# garden.net
KiCad netlist of a schematic drawn in EAGLE
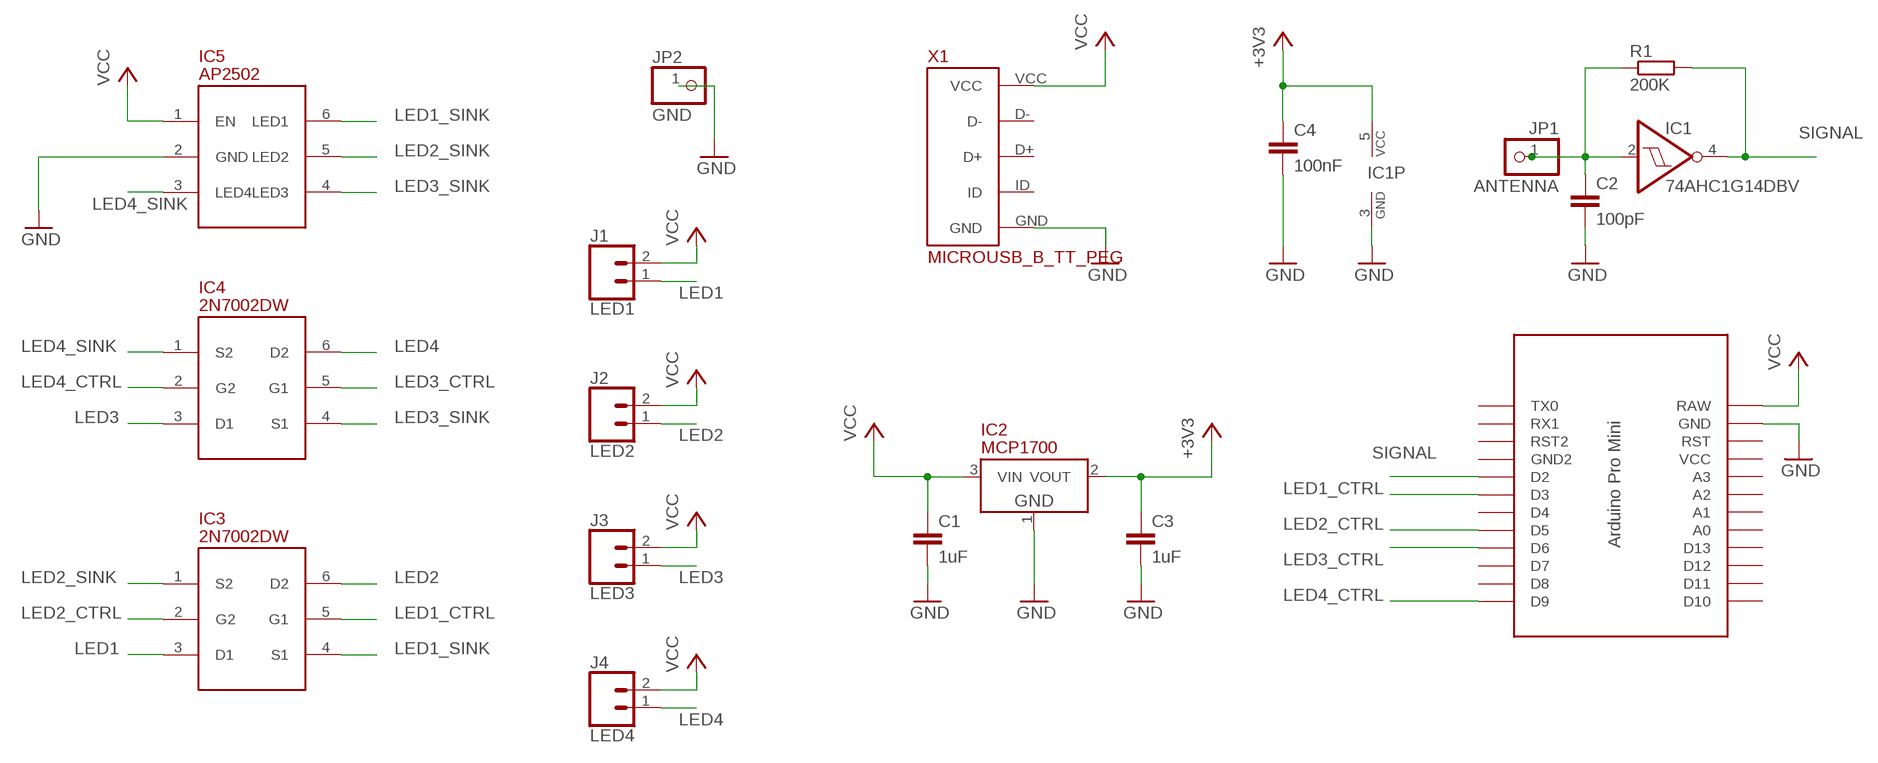
[diagram p0: schematic, sheet 1]

(export (version "E")
  (design (tool "Eeschema 10.0.6"))
  (components
    (comp (ref "C1")
      (value "1uF")
      (footprint "eagle-import:C0805")
      (libsource (lib "eagle-import") (part "C-EUC0805"))
    )
    (comp (ref "C2")
      (value "100pF")
      (footprint "eagle-import:C0805")
      (libsource (lib "eagle-import") (part "C-EUC0805"))
    )
    (comp (ref "C3")
      (value "1uF")
      (footprint "eagle-import:C0805")
      (libsource (lib "eagle-import") (part "C-EUC0805"))
    )
    (comp (ref "C4")
      (value "100nF")
      (footprint "eagle-import:C0805")
      (libsource (lib "eagle-import") (part "C-EUC0805"))
    )
    (comp (ref "IC1")
      (value "74AHC1G14DBV")
      (footprint "eagle-import:SOT23-5")
      (libsource (lib "eagle-import") (part "741G14DBVAHC"))
    )
    (comp (ref "IC2")
      (value "MCP1700")
      (footprint "eagle-import:SOT-23")
      (libsource (lib "eagle-import") (part "MCP1700"))
    )
    (comp (ref "IC3")
      (value "2N7002DW")
      (footprint "eagle-import:SOT363")
      (libsource (lib "eagle-import") (part "2N7002DW"))
    )
    (comp (ref "IC4")
      (value "2N7002DW")
      (footprint "eagle-import:SOT363")
      (libsource (lib "eagle-import") (part "2N7002DW"))
    )
    (comp (ref "IC5")
      (value "AP2502")
      (footprint "eagle-import:SOT-23-6")
      (libsource (lib "eagle-import") (part "AP2502"))
    )
    (comp (ref "J1")
      (value "LED1")
      (footprint "eagle-import:1X02")
      (libsource (lib "eagle-import") (part "CONN_02"))
    )
    (comp (ref "J2")
      (value "LED2")
      (footprint "eagle-import:1X02")
      (libsource (lib "eagle-import") (part "CONN_02"))
    )
    (comp (ref "J3")
      (value "LED3")
      (footprint "eagle-import:1X02")
      (libsource (lib "eagle-import") (part "CONN_02"))
    )
    (comp (ref "J4")
      (value "LED4")
      (footprint "eagle-import:1X02")
      (libsource (lib "eagle-import") (part "CONN_02"))
    )
    (comp (ref "JP1")
      (value "ANTENNA")
      (footprint "eagle-import:1X01")
      (libsource (lib "eagle-import") (part "PINHD-1X1"))
    )
    (comp (ref "JP2")
      (value "GND")
      (footprint "eagle-import:1X01")
      (libsource (lib "eagle-import") (part "PINHD-1X1"))
    )
    (comp (ref "R1")
      (value "200K")
      (footprint "eagle-import:R0805")
      (libsource (lib "eagle-import") (part "R-EU_R0805"))
    )
    (comp (ref "U$1")
      (value "PRO-MINI-TWO-SIDES-ONLY")
      (footprint "eagle-import:PRO-MINI-TWO-SIDES-ONLY")
      (libsource (lib "eagle-import") (part "PRO-MINI-TWO-SIDES-ONLY"))
    )
    (comp (ref "X1")
      (value "MICROUSB_B_TT_PEG")
      (footprint "eagle-import:MICROUSB_B_TT_PEG")
      (libsource (lib "eagle-import") (part "MICROUSB_B_TT_PEG"))
    )
  )
  (nets
    (net (code "1") (name "+3V3") (class "Default")
      (node (ref "C3") (pin "1") (pinfunction "1_1") (pintype "passive"))
      (node (ref "C4") (pin "1") (pinfunction "1_1") (pintype "passive"))
      (node (ref "IC1") (pin "5") (pinfunction "VCC_5") (pintype "power_in"))
      (node (ref "IC2") (pin "2") (pinfunction "VOUT_2") (pintype "output"))
    )
    (net (code "2") (name "/LED1") (class "Default")
      (node (ref "IC3") (pin "3") (pinfunction "D1_3") (pintype "input"))
      (node (ref "J1") (pin "1") (pinfunction "1_1") (pintype "passive"))
    )
    (net (code "3") (name "/LED1_CTRL") (class "Default")
      (node (ref "IC3") (pin "5") (pinfunction "G1_5") (pintype "input"))
      (node (ref "U$1") (pin "D3") (pinfunction "D3_D3") (pintype "bidirectional"))
    )
    (net (code "4") (name "/LED1_SINK") (class "Default")
      (node (ref "IC3") (pin "4") (pinfunction "S1_4") (pintype "output"))
      (node (ref "IC5") (pin "6") (pinfunction "LED1_6") (pintype "output"))
    )
    (net (code "5") (name "/LED2") (class "Default")
      (node (ref "IC3") (pin "6") (pinfunction "D2_6") (pintype "input"))
      (node (ref "J2") (pin "1") (pinfunction "1_1") (pintype "passive"))
    )
    (net (code "6") (name "/LED2_CTRL") (class "Default")
      (node (ref "IC3") (pin "2") (pinfunction "G2_2") (pintype "input"))
      (node (ref "U$1") (pin "D5") (pinfunction "D5_D5") (pintype "bidirectional"))
    )
    (net (code "7") (name "/LED2_SINK") (class "Default")
      (node (ref "IC3") (pin "1") (pinfunction "S2_1") (pintype "output"))
      (node (ref "IC5") (pin "5") (pinfunction "LED2_5") (pintype "output"))
    )
    (net (code "8") (name "/LED3") (class "Default")
      (node (ref "IC4") (pin "3") (pinfunction "D1_3") (pintype "input"))
      (node (ref "J3") (pin "1") (pinfunction "1_1") (pintype "passive"))
    )
    (net (code "9") (name "/LED3_CTRL") (class "Default")
      (node (ref "IC4") (pin "5") (pinfunction "G1_5") (pintype "input"))
      (node (ref "U$1") (pin "D6") (pinfunction "D6_D6") (pintype "bidirectional"))
    )
    (net (code "10") (name "/LED3_SINK") (class "Default")
      (node (ref "IC4") (pin "4") (pinfunction "S1_4") (pintype "output"))
      (node (ref "IC5") (pin "4") (pinfunction "LED3_4") (pintype "output"))
    )
    (net (code "11") (name "/LED4") (class "Default")
      (node (ref "IC4") (pin "6") (pinfunction "D2_6") (pintype "input"))
      (node (ref "J4") (pin "1") (pinfunction "1_1") (pintype "passive"))
    )
    (net (code "12") (name "/LED4_CTRL") (class "Default")
      (node (ref "IC4") (pin "2") (pinfunction "G2_2") (pintype "input"))
      (node (ref "U$1") (pin "D9") (pinfunction "D9_D9") (pintype "bidirectional"))
    )
    (net (code "13") (name "/LED4_SINK") (class "Default")
      (node (ref "IC4") (pin "1") (pinfunction "S2_1") (pintype "output"))
      (node (ref "IC5") (pin "3") (pinfunction "LED4_3") (pintype "output"))
    )
    (net (code "14") (name "/SIGNAL") (class "Default")
      (node (ref "IC1") (pin "4") (pinfunction "O_4") (pintype "output"))
      (node (ref "R1") (pin "2") (pinfunction "2_2") (pintype "passive"))
      (node (ref "U$1") (pin "D2") (pinfunction "D2_D2") (pintype "bidirectional"))
    )
    (net (code "15") (name "GND") (class "Default")
      (node (ref "C1") (pin "2") (pinfunction "2_2") (pintype "passive"))
      (node (ref "C2") (pin "2") (pinfunction "2_2") (pintype "passive"))
      (node (ref "C3") (pin "2") (pinfunction "2_2") (pintype "passive"))
      (node (ref "C4") (pin "2") (pinfunction "2_2") (pintype "passive"))
      (node (ref "IC1") (pin "3") (pinfunction "GND_3") (pintype "power_in"))
      (node (ref "IC2") (pin "1") (pinfunction "GND_1") (pintype "input"))
      (node (ref "IC5") (pin "2") (pinfunction "GND_2") (pintype "input"))
      (node (ref "JP2") (pin "1") (pinfunction "1_1") (pintype "passive"))
      (node (ref "U$1") (pin "GND") (pinfunction "GND_GND") (pintype "input"))
      (node (ref "X1") (pin "GND") (pinfunction "GND_GND") (pintype "power_in"))
    )
    (net (code "16") (name "Net-(IC1A-I)") (class "Default")
      (node (ref "C2") (pin "1") (pinfunction "1_1") (pintype "passive"))
      (node (ref "IC1") (pin "2") (pinfunction "I_2") (pintype "input"))
      (node (ref "JP1") (pin "1") (pinfunction "1_1") (pintype "passive"))
      (node (ref "R1") (pin "1") (pinfunction "1_1") (pintype "passive"))
    )
    (net (code "17") (name "VCC") (class "Default")
      (node (ref "C1") (pin "1") (pinfunction "1_1") (pintype "passive"))
      (node (ref "IC2") (pin "3") (pinfunction "VIN_3") (pintype "input"))
      (node (ref "IC5") (pin "1") (pinfunction "EN_1") (pintype "input"))
      (node (ref "J1") (pin "2") (pinfunction "2_2") (pintype "passive"))
      (node (ref "J2") (pin "2") (pinfunction "2_2") (pintype "passive"))
      (node (ref "J3") (pin "2") (pinfunction "2_2") (pintype "passive"))
      (node (ref "J4") (pin "2") (pinfunction "2_2") (pintype "passive"))
      (node (ref "U$1") (pin "RAW") (pinfunction "RAW_RAW") (pintype "power_in"))
      (node (ref "X1") (pin "VCC") (pinfunction "VCC_VCC") (pintype "power_in"))
    )
    (net (code "18") (name "unconnected-(U$1-GND2-PadGND1)") (class "Default")
      (node (ref "U$1") (pin "GND1") (pinfunction "GND2_GND1") (pintype "bidirectional"))
    )
    (net (code "19") (name "unconnected-(U$1-PadA0)") (class "Default")
      (node (ref "U$1") (pin "A0") (pinfunction "A0_A0") (pintype "bidirectional"))
    )
    (net (code "20") (name "unconnected-(U$1-PadA1)") (class "Default")
      (node (ref "U$1") (pin "A1") (pinfunction "A1_A1") (pintype "bidirectional"))
    )
    (net (code "21") (name "unconnected-(U$1-PadA2)") (class "Default")
      (node (ref "U$1") (pin "A2") (pinfunction "A2_A2") (pintype "bidirectional"))
    )
    (net (code "22") (name "unconnected-(U$1-PadA3)") (class "Default")
      (node (ref "U$1") (pin "A3") (pinfunction "A3_A3") (pintype "bidirectional"))
    )
    (net (code "23") (name "unconnected-(U$1-PadD4)") (class "Default")
      (node (ref "U$1") (pin "D4") (pinfunction "D4_D4") (pintype "bidirectional"))
    )
    (net (code "24") (name "unconnected-(U$1-PadD7)") (class "Default")
      (node (ref "U$1") (pin "D7") (pinfunction "D7_D7") (pintype "bidirectional"))
    )
    (net (code "25") (name "unconnected-(U$1-PadD8)") (class "Default")
      (node (ref "U$1") (pin "D8") (pinfunction "D8_D8") (pintype "bidirectional"))
    )
    (net (code "26") (name "unconnected-(U$1-PadD10)") (class "Default")
      (node (ref "U$1") (pin "D10") (pinfunction "D10_D10") (pintype "bidirectional"))
    )
    (net (code "27") (name "unconnected-(U$1-PadD11)") (class "Default")
      (node (ref "U$1") (pin "D11") (pinfunction "D11_D11") (pintype "bidirectional"))
    )
    (net (code "28") (name "unconnected-(U$1-PadD12)") (class "Default")
      (node (ref "U$1") (pin "D12") (pinfunction "D12_D12") (pintype "bidirectional"))
    )
    (net (code "29") (name "unconnected-(U$1-PadD13)") (class "Default")
      (node (ref "U$1") (pin "D13") (pinfunction "D13_D13") (pintype "bidirectional"))
    )
    (net (code "30") (name "unconnected-(U$1-PadRST)") (class "Default")
      (node (ref "U$1") (pin "RST") (pinfunction "RST_RST") (pintype "bidirectional"))
    )
    (net (code "31") (name "unconnected-(U$1-PadRX1)") (class "Default")
      (node (ref "U$1") (pin "RX1") (pinfunction "RX1_RX1") (pintype "bidirectional"))
    )
    (net (code "32") (name "unconnected-(U$1-PadTX0)") (class "Default")
      (node (ref "U$1") (pin "TX0") (pinfunction "TX0_TX0") (pintype "bidirectional"))
    )
    (net (code "33") (name "unconnected-(U$1-PadVCC)") (class "Default")
      (node (ref "U$1") (pin "VCC") (pinfunction "VCC_VCC") (pintype "bidirectional"))
    )
    (net (code "34") (name "unconnected-(U$1-RST2-PadRST1)") (class "Default")
      (node (ref "U$1") (pin "RST1") (pinfunction "RST2_RST1") (pintype "bidirectional"))
    )
    (net (code "35") (name "unconnected-(X1-PadD+)") (class "Default")
      (node (ref "X1") (pin "D+") (pinfunction "D+_D+") (pintype "bidirectional"))
    )
    (net (code "36") (name "unconnected-(X1-PadD-)") (class "Default")
      (node (ref "X1") (pin "D-") (pinfunction "D-_D-") (pintype "bidirectional"))
    )
    (net (code "37") (name "unconnected-(X1-PadID)") (class "Default")
      (node (ref "X1") (pin "ID") (pinfunction "ID_ID") (pintype "bidirectional"))
    )
  )
)
